# B2B_2.net
KiCad netlist of a schematic drawn in Altium Designer
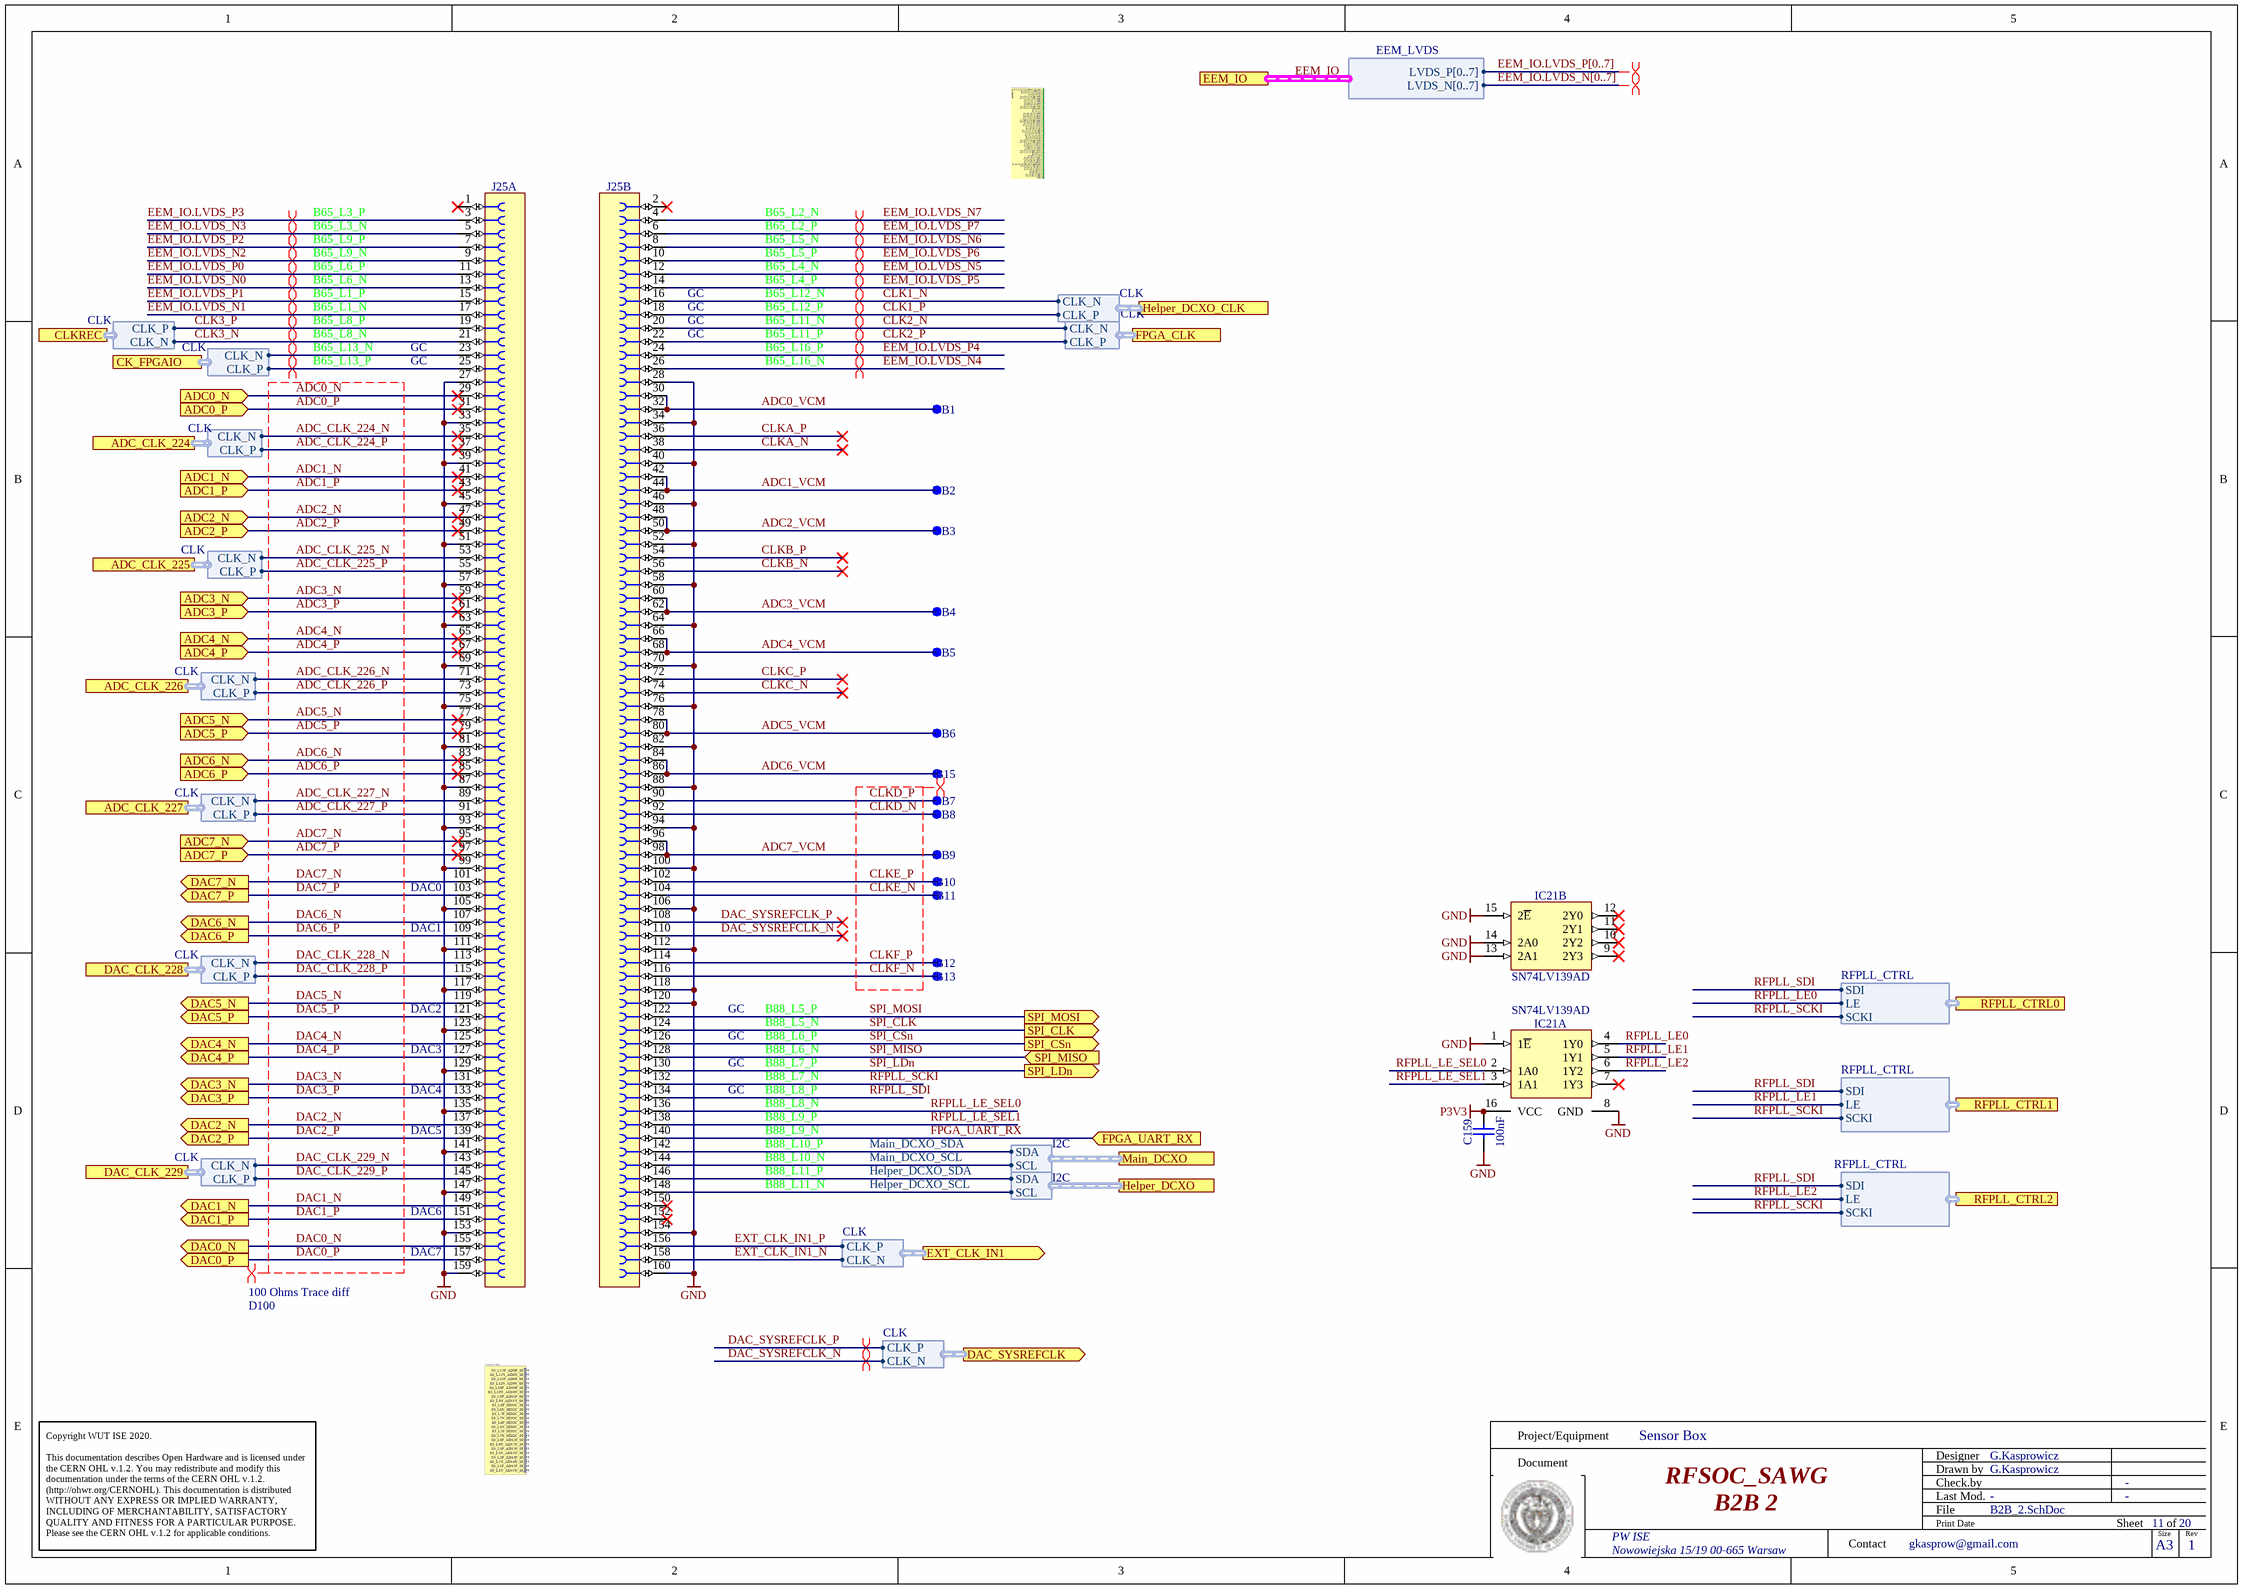
[diagram p0: B2B_2.SchDoc]

(export (version "E")
  (design (tool "Eeschema 10.0.6"))
  (components
    (comp (ref "B1")
      (value "SMD Pad")
      (footprint "C100")
      (description "Through Hole Pad")
      (fields (field (name "PART NUMBER") "SMD_PAD_D1MM") (field (name "AUTHOR") "CERN DEM JLC"))
      (libsource (lib "Eletro-mechanical") (part "Single SMD Pad (Round)"))
    )
    (comp (ref "B2")
      (value "SMD Pad")
      (footprint "C100")
      (description "Through Hole Pad")
      (fields (field (name "PART NUMBER") "SMD_PAD_D1MM") (field (name "AUTHOR") "CERN DEM JLC"))
      (libsource (lib "Eletro-mechanical") (part "Single SMD Pad (Round)"))
    )
    (comp (ref "B3")
      (value "SMD Pad")
      (footprint "C100")
      (description "Through Hole Pad")
      (fields (field (name "PART NUMBER") "SMD_PAD_D1MM") (field (name "AUTHOR") "CERN DEM JLC"))
      (libsource (lib "Eletro-mechanical") (part "Single SMD Pad (Round)"))
    )
    (comp (ref "B4")
      (value "SMD Pad")
      (footprint "C100")
      (description "Through Hole Pad")
      (fields (field (name "PART NUMBER") "SMD_PAD_D1MM") (field (name "AUTHOR") "CERN DEM JLC"))
      (libsource (lib "Eletro-mechanical") (part "Single SMD Pad (Round)"))
    )
    (comp (ref "B5")
      (value "SMD Pad")
      (footprint "C100")
      (description "Through Hole Pad")
      (fields (field (name "PART NUMBER") "SMD_PAD_D1MM") (field (name "AUTHOR") "CERN DEM JLC"))
      (libsource (lib "Eletro-mechanical") (part "Single SMD Pad (Round)"))
    )
    (comp (ref "B6")
      (value "SMD Pad")
      (footprint "C100")
      (description "Through Hole Pad")
      (fields (field (name "PART NUMBER") "SMD_PAD_D1MM") (field (name "AUTHOR") "CERN DEM JLC"))
      (libsource (lib "Eletro-mechanical") (part "Single SMD Pad (Round)"))
    )
    (comp (ref "B7")
      (value "SMD Pad")
      (footprint "C100")
      (description "Through Hole Pad")
      (fields (field (name "PART NUMBER") "SMD_PAD_D1MM") (field (name "AUTHOR") "CERN DEM JLC"))
      (libsource (lib "Eletro-mechanical") (part "Single SMD Pad (Round)"))
    )
    (comp (ref "B8")
      (value "SMD Pad")
      (footprint "C100")
      (description "Through Hole Pad")
      (fields (field (name "PART NUMBER") "SMD_PAD_D1MM") (field (name "AUTHOR") "CERN DEM JLC"))
      (libsource (lib "Eletro-mechanical") (part "Single SMD Pad (Round)"))
    )
    (comp (ref "B9")
      (value "SMD Pad")
      (footprint "C100")
      (description "Through Hole Pad")
      (fields (field (name "PART NUMBER") "SMD_PAD_D1MM") (field (name "AUTHOR") "CERN DEM JLC"))
      (libsource (lib "Eletro-mechanical") (part "Single SMD Pad (Round)"))
    )
    (comp (ref "B10")
      (value "SMD Pad")
      (footprint "C100")
      (description "Through Hole Pad")
      (fields (field (name "PART NUMBER") "SMD_PAD_D1MM") (field (name "AUTHOR") "CERN DEM JLC"))
      (libsource (lib "Eletro-mechanical") (part "Single SMD Pad (Round)"))
    )
    (comp (ref "B11")
      (value "SMD Pad")
      (footprint "C100")
      (description "Through Hole Pad")
      (fields (field (name "PART NUMBER") "SMD_PAD_D1MM") (field (name "AUTHOR") "CERN DEM JLC"))
      (libsource (lib "Eletro-mechanical") (part "Single SMD Pad (Round)"))
    )
    (comp (ref "B12")
      (value "SMD Pad")
      (footprint "C100")
      (description "Through Hole Pad")
      (fields (field (name "PART NUMBER") "SMD_PAD_D1MM") (field (name "AUTHOR") "CERN DEM JLC"))
      (libsource (lib "Eletro-mechanical") (part "Single SMD Pad (Round)"))
    )
    (comp (ref "B13")
      (value "SMD Pad")
      (footprint "C100")
      (description "Through Hole Pad")
      (fields (field (name "PART NUMBER") "SMD_PAD_D1MM") (field (name "AUTHOR") "CERN DEM JLC"))
      (libsource (lib "Eletro-mechanical") (part "Single SMD Pad (Round)"))
    )
    (comp (ref "B15")
      (value "SMD Pad")
      (footprint "C100")
      (description "Through Hole Pad")
      (fields (field (name "PART NUMBER") "SMD_PAD_D1MM") (field (name "AUTHOR") "CERN DEM JLC"))
      (libsource (lib "Eletro-mechanical") (part "Single SMD Pad (Round)"))
    )
    (comp (ref "C159")
      (value "100nF")
      (footprint "CAPC1005X55N")
      (description "Non-polarised capacitor")
      (fields
        (field (name "PART NUMBER") "CC0402_100NF_16V_10%_X7R")
        (field (name "VOLTAGE") "16V")
        (field (name "AUTHOR") "CERN DEM JLC")
      )
      (libsource (lib "Capacitors") (part "Capacitor - non polarized"))
    )
    (comp (ref "IC21")
      (value "SN74LV139AD")
      (footprint "SOIC127P600X175-16N")
      (description "Dual 2-to-4 line decoder/demultiplexer")
      (fields (field (name "MANUFACTURER") "TEXAS INSTRUMENTS") (field (name "AUTHOR") "CERN DEM JLC"))
      (libsource (lib "ICs And Semiconductors") (part "74139_a"))
    )
    (comp (ref "J25")
      (value "Socket 160")
      (footprint "SAMTEC_SS5-80-3.00-L-D-K")
      (description "Connector 160 Female")
      (fields
        (field (name "PART NUMBER") "SAMTEC_SS5-80-3.00-L-D-K")
        (field (name "MANUFACTURER") "SAMTEC")
        (field (name "AUTHOR") "CERN DEM BC")
      )
      (libsource (lib "Connectors") (part "Connector 160 Female"))
    )
  )
  (nets
    (net (code "5") (name "/ADC0_N") (class "Default")
      (node (ref "J25") (pin "29") (pinfunction "29_29") (pintype "bidirectional+no_connect"))
    )
    (net (code "6") (name "/ADC0_P") (class "Default")
      (node (ref "J25") (pin "31") (pinfunction "31_31") (pintype "bidirectional+no_connect"))
    )
    (net (code "7") (name "/ADC0_VCM") (class "Default")
      (node (ref "B1") (pin "1") (pinfunction "1_1") (pintype "bidirectional"))
      (node (ref "J25") (pin "30") (pinfunction "30_30") (pintype "bidirectional"))
      (node (ref "J25") (pin "32") (pinfunction "32_32") (pintype "bidirectional"))
    )
    (net (code "8") (name "/ADC1_N") (class "Default")
      (node (ref "J25") (pin "41") (pinfunction "41_41") (pintype "bidirectional+no_connect"))
    )
    (net (code "9") (name "/ADC1_P") (class "Default")
      (node (ref "J25") (pin "43") (pinfunction "43_43") (pintype "bidirectional+no_connect"))
    )
    (net (code "10") (name "/ADC1_VCM") (class "Default")
      (node (ref "B2") (pin "1") (pinfunction "1_1") (pintype "bidirectional"))
      (node (ref "J25") (pin "42") (pinfunction "42_42") (pintype "bidirectional"))
      (node (ref "J25") (pin "44") (pinfunction "44_44") (pintype "bidirectional"))
    )
    (net (code "11") (name "/ADC2_N") (class "Default")
      (node (ref "J25") (pin "47") (pinfunction "47_47") (pintype "bidirectional+no_connect"))
    )
    (net (code "12") (name "/ADC2_P") (class "Default")
      (node (ref "J25") (pin "49") (pinfunction "49_49") (pintype "bidirectional+no_connect"))
    )
    (net (code "13") (name "/ADC2_VCM") (class "Default")
      (node (ref "B3") (pin "1") (pinfunction "1_1") (pintype "bidirectional"))
      (node (ref "J25") (pin "48") (pinfunction "48_48") (pintype "bidirectional"))
      (node (ref "J25") (pin "50") (pinfunction "50_50") (pintype "bidirectional"))
    )
    (net (code "14") (name "/ADC3_N") (class "Default")
      (node (ref "J25") (pin "59") (pinfunction "59_59") (pintype "bidirectional+no_connect"))
    )
    (net (code "15") (name "/ADC3_P") (class "Default")
      (node (ref "J25") (pin "61") (pinfunction "61_61") (pintype "bidirectional+no_connect"))
    )
    (net (code "16") (name "/ADC3_VCM") (class "Default")
      (node (ref "B4") (pin "1") (pinfunction "1_1") (pintype "bidirectional"))
      (node (ref "J25") (pin "60") (pinfunction "60_60") (pintype "bidirectional"))
      (node (ref "J25") (pin "62") (pinfunction "62_62") (pintype "bidirectional"))
    )
    (net (code "17") (name "/ADC4_N") (class "Default")
      (node (ref "J25") (pin "65") (pinfunction "65_65") (pintype "bidirectional+no_connect"))
    )
    (net (code "18") (name "/ADC4_P") (class "Default")
      (node (ref "J25") (pin "67") (pinfunction "67_67") (pintype "bidirectional+no_connect"))
    )
    (net (code "19") (name "/ADC4_VCM") (class "Default")
      (node (ref "B5") (pin "1") (pinfunction "1_1") (pintype "bidirectional"))
      (node (ref "J25") (pin "66") (pinfunction "66_66") (pintype "bidirectional"))
      (node (ref "J25") (pin "68") (pinfunction "68_68") (pintype "bidirectional"))
    )
    (net (code "20") (name "/ADC5_N") (class "Default")
      (node (ref "J25") (pin "77") (pinfunction "77_77") (pintype "bidirectional+no_connect"))
    )
    (net (code "21") (name "/ADC5_P") (class "Default")
      (node (ref "J25") (pin "79") (pinfunction "79_79") (pintype "bidirectional+no_connect"))
    )
    (net (code "22") (name "/ADC5_VCM") (class "Default")
      (node (ref "B6") (pin "1") (pinfunction "1_1") (pintype "bidirectional"))
      (node (ref "J25") (pin "78") (pinfunction "78_78") (pintype "bidirectional"))
      (node (ref "J25") (pin "80") (pinfunction "80_80") (pintype "bidirectional"))
    )
    (net (code "23") (name "/ADC6_N") (class "Default")
      (node (ref "J25") (pin "83") (pinfunction "83_83") (pintype "bidirectional+no_connect"))
    )
    (net (code "24") (name "/ADC6_P") (class "Default")
      (node (ref "J25") (pin "85") (pinfunction "85_85") (pintype "bidirectional+no_connect"))
    )
    (net (code "25") (name "/ADC6_VCM") (class "Default")
      (node (ref "B15") (pin "1") (pinfunction "1_1") (pintype "bidirectional"))
      (node (ref "J25") (pin "84") (pinfunction "84_84") (pintype "bidirectional"))
      (node (ref "J25") (pin "86") (pinfunction "86_86") (pintype "bidirectional"))
    )
    (net (code "26") (name "/ADC7_N") (class "Default")
      (node (ref "J25") (pin "95") (pinfunction "95_95") (pintype "bidirectional+no_connect"))
    )
    (net (code "27") (name "/ADC7_P") (class "Default")
      (node (ref "J25") (pin "97") (pinfunction "97_97") (pintype "bidirectional+no_connect"))
    )
    (net (code "28") (name "/ADC7_VCM") (class "Default")
      (node (ref "B9") (pin "1") (pinfunction "1_1") (pintype "bidirectional"))
      (node (ref "J25") (pin "96") (pinfunction "96_96") (pintype "bidirectional"))
      (node (ref "J25") (pin "98") (pinfunction "98_98") (pintype "bidirectional"))
    )
    (net (code "29") (name "/ADC_CLK_224_N") (class "Default")
      (node (ref "J25") (pin "35") (pinfunction "35_35") (pintype "bidirectional+no_connect"))
    )
    (net (code "30") (name "/ADC_CLK_224_P") (class "Default")
      (node (ref "J25") (pin "37") (pinfunction "37_37") (pintype "bidirectional+no_connect"))
    )
    (net (code "31") (name "/ADC_CLK_225_N") (class "Default")
      (node (ref "J25") (pin "53") (pinfunction "53_53") (pintype "bidirectional"))
    )
    (net (code "32") (name "/ADC_CLK_225_P") (class "Default")
      (node (ref "J25") (pin "55") (pinfunction "55_55") (pintype "bidirectional"))
    )
    (net (code "33") (name "/ADC_CLK_226_N") (class "Default")
      (node (ref "J25") (pin "71") (pinfunction "71_71") (pintype "bidirectional"))
    )
    (net (code "34") (name "/ADC_CLK_226_P") (class "Default")
      (node (ref "J25") (pin "73") (pinfunction "73_73") (pintype "bidirectional"))
    )
    (net (code "35") (name "/ADC_CLK_227_N") (class "Default")
      (node (ref "J25") (pin "89") (pinfunction "89_89") (pintype "bidirectional"))
    )
    (net (code "36") (name "/ADC_CLK_227_P") (class "Default")
      (node (ref "J25") (pin "91") (pinfunction "91_91") (pintype "bidirectional"))
    )
    (net (code "37") (name "/CLK1_N") (class "Default")
      (node (ref "J25") (pin "16") (pinfunction "16_16") (pintype "bidirectional"))
    )
    (net (code "38") (name "/CLK1_P") (class "Default")
      (node (ref "J25") (pin "18") (pinfunction "18_18") (pintype "bidirectional"))
    )
    (net (code "39") (name "/CLK2_N") (class "Default")
      (node (ref "J25") (pin "20") (pinfunction "20_20") (pintype "bidirectional"))
    )
    (net (code "40") (name "/CLK2_P") (class "Default")
      (node (ref "J25") (pin "22") (pinfunction "22_22") (pintype "bidirectional"))
    )
    (net (code "41") (name "/CLK3_N") (class "Default")
      (node (ref "J25") (pin "21") (pinfunction "21_21") (pintype "bidirectional"))
    )
    (net (code "42") (name "/CLK3_P") (class "Default")
      (node (ref "J25") (pin "19") (pinfunction "19_19") (pintype "bidirectional"))
    )
    (net (code "43") (name "/CLKA_N") (class "Default")
      (node (ref "J25") (pin "38") (pinfunction "38_38") (pintype "bidirectional+no_connect"))
    )
    (net (code "44") (name "/CLKA_P") (class "Default")
      (node (ref "J25") (pin "36") (pinfunction "36_36") (pintype "bidirectional+no_connect"))
    )
    (net (code "45") (name "/CLKB_N") (class "Default")
      (node (ref "J25") (pin "56") (pinfunction "56_56") (pintype "bidirectional+no_connect"))
    )
    (net (code "46") (name "/CLKB_P") (class "Default")
      (node (ref "J25") (pin "54") (pinfunction "54_54") (pintype "bidirectional+no_connect"))
    )
    (net (code "47") (name "/CLKC_N") (class "Default")
      (node (ref "J25") (pin "74") (pinfunction "74_74") (pintype "bidirectional+no_connect"))
    )
    (net (code "48") (name "/CLKC_P") (class "Default")
      (node (ref "J25") (pin "72") (pinfunction "72_72") (pintype "bidirectional+no_connect"))
    )
    (net (code "49") (name "/CLKD_N") (class "Default")
      (node (ref "B8") (pin "1") (pinfunction "1_1") (pintype "bidirectional"))
      (node (ref "J25") (pin "92") (pinfunction "92_92") (pintype "bidirectional"))
    )
    (net (code "50") (name "/CLKD_P") (class "Default")
      (node (ref "B7") (pin "1") (pinfunction "1_1") (pintype "bidirectional"))
      (node (ref "J25") (pin "90") (pinfunction "90_90") (pintype "bidirectional"))
    )
    (net (code "51") (name "/CLKE_N") (class "Default")
      (node (ref "B11") (pin "1") (pinfunction "1_1") (pintype "bidirectional"))
      (node (ref "J25") (pin "104") (pinfunction "104_104") (pintype "bidirectional"))
    )
    (net (code "52") (name "/CLKE_P") (class "Default")
      (node (ref "B10") (pin "1") (pinfunction "1_1") (pintype "bidirectional"))
      (node (ref "J25") (pin "102") (pinfunction "102_102") (pintype "bidirectional"))
    )
    (net (code "53") (name "/CLKF_N") (class "Default")
      (node (ref "B13") (pin "1") (pinfunction "1_1") (pintype "bidirectional"))
      (node (ref "J25") (pin "116") (pinfunction "116_116") (pintype "bidirectional"))
    )
    (net (code "54") (name "/CLKF_P") (class "Default")
      (node (ref "B12") (pin "1") (pinfunction "1_1") (pintype "bidirectional"))
      (node (ref "J25") (pin "114") (pinfunction "114_114") (pintype "bidirectional"))
    )
    (net (code "55") (name "/DAC0_N") (class "Default")
      (node (ref "J25") (pin "155") (pinfunction "155_155") (pintype "bidirectional"))
    )
    (net (code "56") (name "/DAC0_P") (class "Default")
      (node (ref "J25") (pin "157") (pinfunction "157_157") (pintype "bidirectional"))
    )
    (net (code "57") (name "/DAC1_N") (class "Default")
      (node (ref "J25") (pin "149") (pinfunction "149_149") (pintype "bidirectional"))
    )
    (net (code "58") (name "/DAC1_P") (class "Default")
      (node (ref "J25") (pin "151") (pinfunction "151_151") (pintype "bidirectional"))
    )
    (net (code "59") (name "/DAC2_N") (class "Default")
      (node (ref "J25") (pin "137") (pinfunction "137_137") (pintype "bidirectional"))
    )
    (net (code "60") (name "/DAC2_P") (class "Default")
      (node (ref "J25") (pin "139") (pinfunction "139_139") (pintype "bidirectional"))
    )
    (net (code "61") (name "/DAC3_N") (class "Default")
      (node (ref "J25") (pin "131") (pinfunction "131_131") (pintype "bidirectional"))
    )
    (net (code "62") (name "/DAC3_P") (class "Default")
      (node (ref "J25") (pin "133") (pinfunction "133_133") (pintype "bidirectional"))
    )
    (net (code "63") (name "/DAC4_N") (class "Default")
      (node (ref "J25") (pin "125") (pinfunction "125_125") (pintype "bidirectional"))
    )
    (net (code "64") (name "/DAC4_P") (class "Default")
      (node (ref "J25") (pin "127") (pinfunction "127_127") (pintype "bidirectional"))
    )
    (net (code "65") (name "/DAC5_N") (class "Default")
      (node (ref "J25") (pin "119") (pinfunction "119_119") (pintype "bidirectional"))
    )
    (net (code "66") (name "/DAC5_P") (class "Default")
      (node (ref "J25") (pin "121") (pinfunction "121_121") (pintype "bidirectional"))
    )
    (net (code "67") (name "/DAC6_N") (class "Default")
      (node (ref "J25") (pin "107") (pinfunction "107_107") (pintype "bidirectional"))
    )
    (net (code "68") (name "/DAC6_P") (class "Default")
      (node (ref "J25") (pin "109") (pinfunction "109_109") (pintype "bidirectional"))
    )
    (net (code "69") (name "/DAC7_N") (class "Default")
      (node (ref "J25") (pin "101") (pinfunction "101_101") (pintype "bidirectional"))
    )
    (net (code "70") (name "/DAC7_P") (class "Default")
      (node (ref "J25") (pin "103") (pinfunction "103_103") (pintype "bidirectional"))
    )
    (net (code "71") (name "/DAC_CLK_228_N") (class "Default")
      (node (ref "J25") (pin "113") (pinfunction "113_113") (pintype "bidirectional"))
    )
    (net (code "72") (name "/DAC_CLK_228_P") (class "Default")
      (node (ref "J25") (pin "115") (pinfunction "115_115") (pintype "bidirectional"))
    )
    (net (code "73") (name "/DAC_CLK_229_N") (class "Default")
      (node (ref "J25") (pin "143") (pinfunction "143_143") (pintype "bidirectional"))
    )
    (net (code "74") (name "/DAC_CLK_229_P") (class "Default")
      (node (ref "J25") (pin "145") (pinfunction "145_145") (pintype "bidirectional"))
    )
    (net (code "75") (name "/DAC_SYSREFCLK_N") (class "Default")
      (node (ref "J25") (pin "110") (pinfunction "110_110") (pintype "bidirectional"))
    )
    (net (code "76") (name "/DAC_SYSREFCLK_P") (class "Default")
      (node (ref "J25") (pin "108") (pinfunction "108_108") (pintype "bidirectional"))
    )
    (net (code "77") (name "/EEM_IO.LVDS_N0") (class "Default")
      (node (ref "J25") (pin "13") (pinfunction "13_13") (pintype "bidirectional"))
    )
    (net (code "78") (name "/EEM_IO.LVDS_N1") (class "Default")
      (node (ref "J25") (pin "17") (pinfunction "17_17") (pintype "bidirectional"))
    )
    (net (code "79") (name "/EEM_IO.LVDS_N2") (class "Default")
      (node (ref "J25") (pin "9") (pinfunction "9_9") (pintype "bidirectional"))
    )
    (net (code "80") (name "/EEM_IO.LVDS_N3") (class "Default")
      (node (ref "J25") (pin "5") (pinfunction "5_5") (pintype "bidirectional"))
    )
    (net (code "81") (name "/EEM_IO.LVDS_N4") (class "Default")
      (node (ref "J25") (pin "26") (pinfunction "26_26") (pintype "bidirectional"))
    )
    (net (code "82") (name "/EEM_IO.LVDS_N5") (class "Default")
      (node (ref "J25") (pin "12") (pinfunction "12_12") (pintype "bidirectional"))
    )
    (net (code "83") (name "/EEM_IO.LVDS_N6") (class "Default")
      (node (ref "J25") (pin "8") (pinfunction "8_8") (pintype "bidirectional"))
    )
    (net (code "84") (name "/EEM_IO.LVDS_N7") (class "Default")
      (node (ref "J25") (pin "4") (pinfunction "4_4") (pintype "bidirectional"))
    )
    (net (code "86") (name "/EEM_IO.LVDS_P0") (class "Default")
      (node (ref "J25") (pin "11") (pinfunction "11_11") (pintype "bidirectional"))
    )
    (net (code "87") (name "/EEM_IO.LVDS_P1") (class "Default")
      (node (ref "J25") (pin "15") (pinfunction "15_15") (pintype "bidirectional"))
    )
    (net (code "88") (name "/EEM_IO.LVDS_P2") (class "Default")
      (node (ref "J25") (pin "7") (pinfunction "7_7") (pintype "bidirectional"))
    )
    (net (code "89") (name "/EEM_IO.LVDS_P3") (class "Default")
      (node (ref "J25") (pin "3") (pinfunction "3_3") (pintype "bidirectional"))
    )
    (net (code "90") (name "/EEM_IO.LVDS_P4") (class "Default")
      (node (ref "J25") (pin "24") (pinfunction "24_24") (pintype "bidirectional"))
    )
    (net (code "91") (name "/EEM_IO.LVDS_P5") (class "Default")
      (node (ref "J25") (pin "14") (pinfunction "14_14") (pintype "bidirectional"))
    )
    (net (code "92") (name "/EEM_IO.LVDS_P6") (class "Default")
      (node (ref "J25") (pin "10") (pinfunction "10_10") (pintype "bidirectional"))
    )
    (net (code "93") (name "/EEM_IO.LVDS_P7") (class "Default")
      (node (ref "J25") (pin "6") (pinfunction "6_6") (pintype "bidirectional"))
    )
    (net (code "94") (name "/EXT_CLK_IN1_N") (class "Default")
      (node (ref "J25") (pin "158") (pinfunction "158_158") (pintype "bidirectional"))
    )
    (net (code "95") (name "/EXT_CLK_IN1_P") (class "Default")
      (node (ref "J25") (pin "156") (pinfunction "156_156") (pintype "bidirectional"))
    )
    (net (code "96") (name "/FPGA_UART_RX") (class "Default")
      (node (ref "J25") (pin "140") (pinfunction "140_140") (pintype "bidirectional"))
    )
    (net (code "97") (name "/Helper_DCXO_SCL") (class "Default")
      (node (ref "J25") (pin "148") (pinfunction "148_148") (pintype "bidirectional"))
    )
    (net (code "98") (name "/Helper_DCXO_SDA") (class "Default")
      (node (ref "J25") (pin "146") (pinfunction "146_146") (pintype "bidirectional"))
    )
    (net (code "99") (name "/Main_DCXO_SCL") (class "Default")
      (node (ref "J25") (pin "144") (pinfunction "144_144") (pintype "bidirectional"))
    )
    (net (code "100") (name "/Main_DCXO_SDA") (class "Default")
      (node (ref "J25") (pin "142") (pinfunction "142_142") (pintype "bidirectional"))
    )
    (net (code "101") (name "/RFPLL_LE0") (class "Default")
      (node (ref "IC21") (pin "4") (pinfunction "1Y0_4") (pintype "output"))
    )
    (net (code "102") (name "/RFPLL_LE1") (class "Default")
      (node (ref "IC21") (pin "5") (pinfunction "1Y1_5") (pintype "output"))
    )
    (net (code "103") (name "/RFPLL_LE2") (class "Default")
      (node (ref "IC21") (pin "6") (pinfunction "1Y2_6") (pintype "output"))
    )
    (net (code "104") (name "/RFPLL_LE_SEL0") (class "Default")
      (node (ref "IC21") (pin "2") (pinfunction "1A0_2") (pintype "input"))
      (node (ref "J25") (pin "136") (pinfunction "136_136") (pintype "bidirectional"))
    )
    (net (code "105") (name "/RFPLL_LE_SEL1") (class "Default")
      (node (ref "IC21") (pin "3") (pinfunction "1A1_3") (pintype "input"))
      (node (ref "J25") (pin "138") (pinfunction "138_138") (pintype "bidirectional"))
    )
    (net (code "106") (name "/RFPLL_SCKI") (class "Default")
      (node (ref "J25") (pin "132") (pinfunction "132_132") (pintype "bidirectional"))
    )
    (net (code "107") (name "/RFPLL_SDI") (class "Default")
      (node (ref "J25") (pin "134") (pinfunction "134_134") (pintype "bidirectional"))
    )
    (net (code "108") (name "/SPI_CLK") (class "Default")
      (node (ref "J25") (pin "124") (pinfunction "124_124") (pintype "bidirectional"))
    )
    (net (code "109") (name "/SPI_CSn") (class "Default")
      (node (ref "J25") (pin "126") (pinfunction "126_126") (pintype "bidirectional"))
    )
    (net (code "110") (name "/SPI_LDn") (class "Default")
      (node (ref "J25") (pin "130") (pinfunction "130_130") (pintype "bidirectional"))
    )
    (net (code "111") (name "/SPI_MISO") (class "Default")
      (node (ref "J25") (pin "128") (pinfunction "128_128") (pintype "bidirectional"))
    )
    (net (code "112") (name "/SPI_MOSI") (class "Default")
      (node (ref "J25") (pin "122") (pinfunction "122_122") (pintype "bidirectional"))
    )
    (net (code "118") (name "GND") (class "Default")
      (node (ref "C159") (pin "1") (pinfunction "1_1") (pintype "passive"))
      (node (ref "IC21") (pin "1") (pinfunction "1~{E}_1") (pintype "input"))
      (node (ref "IC21") (pin "13") (pinfunction "2A1_13") (pintype "input"))
      (node (ref "IC21") (pin "14") (pinfunction "2A0_14") (pintype "input"))
      (node (ref "IC21") (pin "15") (pinfunction "2~{E}_15") (pintype "input"))
      (node (ref "IC21") (pin "8") (pinfunction "GND_8") (pintype "power_in"))
      (node (ref "J25") (pin "100") (pinfunction "100_100") (pintype "bidirectional"))
      (node (ref "J25") (pin "105") (pinfunction "105_105") (pintype "bidirectional"))
      (node (ref "J25") (pin "106") (pinfunction "106_106") (pintype "bidirectional"))
      (node (ref "J25") (pin "111") (pinfunction "111_111") (pintype "bidirectional"))
      (node (ref "J25") (pin "112") (pinfunction "112_112") (pintype "bidirectional"))
      (node (ref "J25") (pin "117") (pinfunction "117_117") (pintype "bidirectional"))
      (node (ref "J25") (pin "118") (pinfunction "118_118") (pintype "bidirectional"))
      (node (ref "J25") (pin "120") (pinfunction "120_120") (pintype "bidirectional"))
      (node (ref "J25") (pin "123") (pinfunction "123_123") (pintype "bidirectional"))
      (node (ref "J25") (pin "129") (pinfunction "129_129") (pintype "bidirectional"))
      (node (ref "J25") (pin "135") (pinfunction "135_135") (pintype "bidirectional"))
      (node (ref "J25") (pin "141") (pinfunction "141_141") (pintype "bidirectional"))
      (node (ref "J25") (pin "147") (pinfunction "147_147") (pintype "bidirectional"))
      (node (ref "J25") (pin "153") (pinfunction "153_153") (pintype "bidirectional"))
      (node (ref "J25") (pin "154") (pinfunction "154_154") (pintype "bidirectional"))
      (node (ref "J25") (pin "159") (pinfunction "159_159") (pintype "bidirectional"))
      (node (ref "J25") (pin "160") (pinfunction "160_160") (pintype "bidirectional"))
      (node (ref "J25") (pin "27") (pinfunction "27_27") (pintype "bidirectional"))
      (node (ref "J25") (pin "28") (pinfunction "28_28") (pintype "bidirectional"))
      (node (ref "J25") (pin "33") (pinfunction "33_33") (pintype "bidirectional"))
      (node (ref "J25") (pin "34") (pinfunction "34_34") (pintype "bidirectional"))
      (node (ref "J25") (pin "39") (pinfunction "39_39") (pintype "bidirectional"))
      (node (ref "J25") (pin "40") (pinfunction "40_40") (pintype "bidirectional"))
      (node (ref "J25") (pin "45") (pinfunction "45_45") (pintype "bidirectional"))
      (node (ref "J25") (pin "46") (pinfunction "46_46") (pintype "bidirectional"))
      (node (ref "J25") (pin "51") (pinfunction "51_51") (pintype "bidirectional"))
      (node (ref "J25") (pin "52") (pinfunction "52_52") (pintype "bidirectional"))
      (node (ref "J25") (pin "57") (pinfunction "57_57") (pintype "bidirectional"))
      (node (ref "J25") (pin "58") (pinfunction "58_58") (pintype "bidirectional"))
      (node (ref "J25") (pin "63") (pinfunction "63_63") (pintype "bidirectional"))
      (node (ref "J25") (pin "64") (pinfunction "64_64") (pintype "bidirectional"))
      (node (ref "J25") (pin "69") (pinfunction "69_69") (pintype "bidirectional"))
      (node (ref "J25") (pin "70") (pinfunction "70_70") (pintype "bidirectional"))
      (node (ref "J25") (pin "75") (pinfunction "75_75") (pintype "bidirectional"))
      (node (ref "J25") (pin "76") (pinfunction "76_76") (pintype "bidirectional"))
      (node (ref "J25") (pin "81") (pinfunction "81_81") (pintype "bidirectional"))
      (node (ref "J25") (pin "82") (pinfunction "82_82") (pintype "bidirectional"))
      (node (ref "J25") (pin "87") (pinfunction "87_87") (pintype "bidirectional"))
      (node (ref "J25") (pin "88") (pinfunction "88_88") (pintype "bidirectional"))
      (node (ref "J25") (pin "93") (pinfunction "93_93") (pintype "bidirectional"))
      (node (ref "J25") (pin "94") (pinfunction "94_94") (pintype "bidirectional"))
      (node (ref "J25") (pin "99") (pinfunction "99_99") (pintype "bidirectional"))
    )
    (net (code "119") (name "P3V3") (class "Default")
      (node (ref "C159") (pin "2") (pinfunction "2_2") (pintype "passive"))
      (node (ref "IC21") (pin "16") (pinfunction "VCC_16") (pintype "power_in"))
    )
    (net (code "120") (name "unconnected-(IC21A-1Y3-Pad7)") (class "Default")
      (node (ref "IC21") (pin "7") (pinfunction "1Y3_7") (pintype "output+no_connect"))
    )
    (net (code "121") (name "unconnected-(IC21B-2Y0-Pad12)") (class "Default")
      (node (ref "IC21") (pin "12") (pinfunction "2Y0_12") (pintype "output+no_connect"))
    )
    (net (code "122") (name "unconnected-(IC21B-2Y1-Pad11)") (class "Default")
      (node (ref "IC21") (pin "11") (pinfunction "2Y1_11") (pintype "output+no_connect"))
    )
    (net (code "123") (name "unconnected-(IC21B-2Y2-Pad10)") (class "Default")
      (node (ref "IC21") (pin "10") (pinfunction "2Y2_10") (pintype "output+no_connect"))
    )
    (net (code "124") (name "unconnected-(IC21B-2Y3-Pad9)") (class "Default")
      (node (ref "IC21") (pin "9") (pinfunction "2Y3_9") (pintype "output+no_connect"))
    )
    (net (code "125") (name "unconnected-(J25-Pad1)") (class "Default")
      (node (ref "J25") (pin "1") (pinfunction "1_1") (pintype "bidirectional+no_connect"))
    )
    (net (code "126") (name "unconnected-(J25-Pad2)") (class "Default")
      (node (ref "J25") (pin "2") (pinfunction "2_2") (pintype "bidirectional+no_connect"))
    )
    (net (code "127") (name "unconnected-(J25-Pad23)") (class "Default")
      (node (ref "J25") (pin "23") (pinfunction "23_23") (pintype "bidirectional"))
    )
    (net (code "128") (name "unconnected-(J25-Pad25)") (class "Default")
      (node (ref "J25") (pin "25") (pinfunction "25_25") (pintype "bidirectional"))
    )
    (net (code "129") (name "unconnected-(J25-Pad150)") (class "Default")
      (node (ref "J25") (pin "150") (pinfunction "150_150") (pintype "bidirectional+no_connect"))
    )
    (net (code "130") (name "unconnected-(J25-Pad152)") (class "Default")
      (node (ref "J25") (pin "152") (pinfunction "152_152") (pintype "bidirectional+no_connect"))
    )
  )
)
